# control-bridge.net
KiCad netlist of a schematic drawn in EAGLE
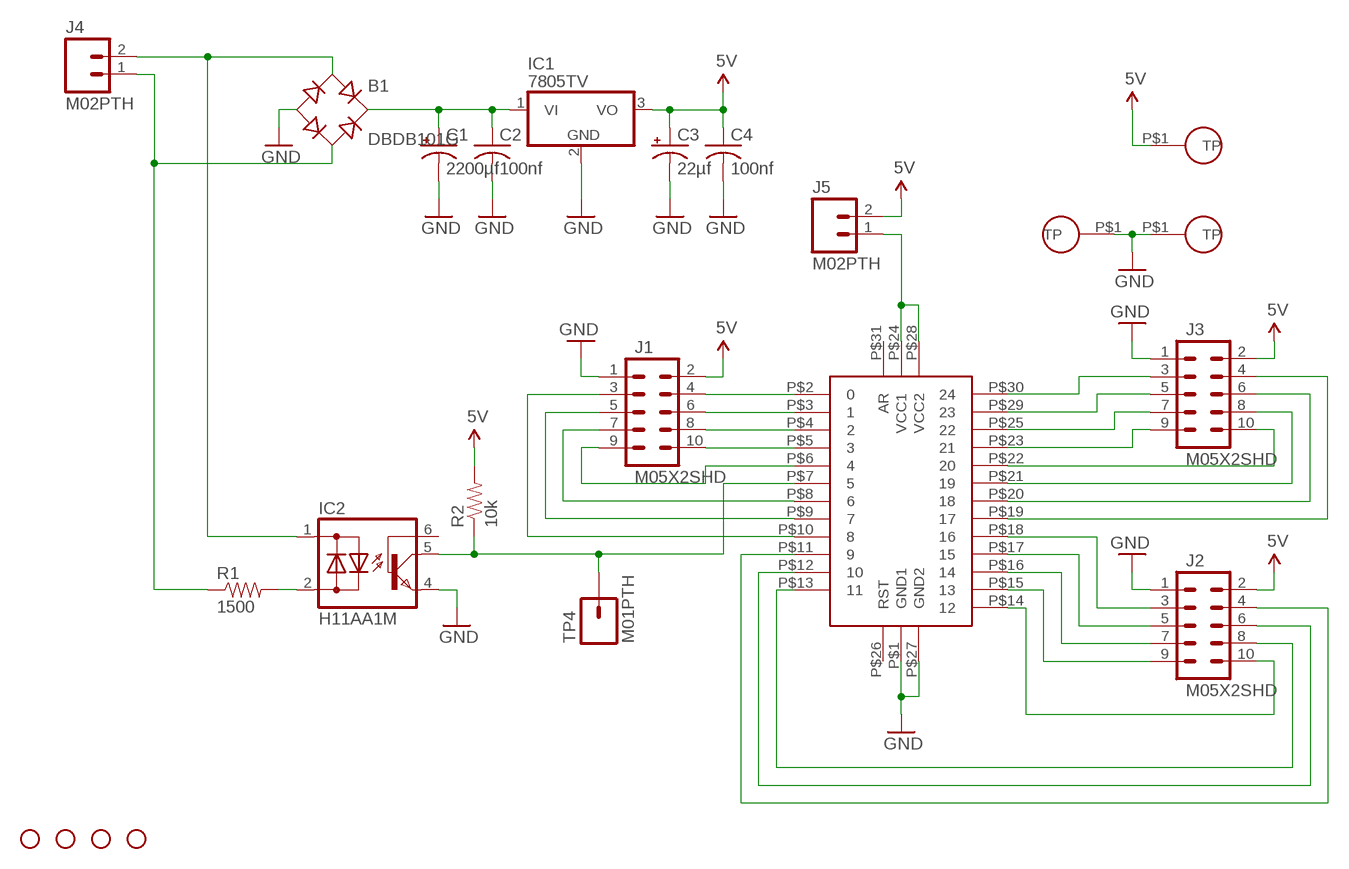
[diagram p0: schematic, sheet 1]

(export (version "E")
  (design (tool "Eeschema 10.0.6"))
  (components
    (comp (ref "B1")
      (value "DBDB101G")
      (footprint "eagle-import:DB")
      (libsource (lib "eagle-import") (part "DB?GDB101"))
    )
    (comp (ref "C1")
      (value "2200µf")
      (footprint "eagle-import:E5-13")
      (libsource (lib "eagle-import") (part "CPOL-USE5-13"))
    )
    (comp (ref "C2")
      (value "100nf")
      (footprint "eagle-import:C025-030X050")
      (libsource (lib "eagle-import") (part "C-US025-030X050"))
    )
    (comp (ref "C3")
      (value "22µf")
      (footprint "eagle-import:E5-8,5")
      (libsource (lib "eagle-import") (part "CPOL-USE5-8.5"))
    )
    (comp (ref "C4")
      (value "100nf")
      (footprint "eagle-import:C025-030X050")
      (libsource (lib "eagle-import") (part "C-US025-030X050"))
    )
    (comp (ref "IC1")
      (value "7805TV")
      (footprint "eagle-import:TO220V")
      (libsource (lib "eagle-import") (part "78TV05"))
    )
    (comp (ref "IC2")
      (value "H11AA1M")
      (footprint "eagle-import:DIL06")
      (fields (field (name "MF") "Fairchild"))
      (libsource (lib "eagle-import") (part "H11AA1M"))
    )
    (comp (ref "J1")
      (value "M05X2SHD")
      (footprint "eagle-import:2X5-SHROUDED")
      (libsource (lib "eagle-import") (part "M05X2SHD"))
    )
    (comp (ref "J2")
      (value "M05X2SHD")
      (footprint "eagle-import:2X5-SHROUDED")
      (libsource (lib "eagle-import") (part "M05X2SHD"))
    )
    (comp (ref "J3")
      (value "M05X2SHD")
      (footprint "eagle-import:2X5-SHROUDED")
      (libsource (lib "eagle-import") (part "M05X2SHD"))
    )
    (comp (ref "J4")
      (value "M02PTH")
      (footprint "eagle-import:1X02")
      (libsource (lib "eagle-import") (part "M02PTH"))
    )
    (comp (ref "J5")
      (value "M02PTH")
      (footprint "eagle-import:1X02")
      (libsource (lib "eagle-import") (part "M02PTH"))
    )
    (comp (ref "R1")
      (value "1500")
      (footprint "eagle-import:AXIAL-0.4")
      (libsource (lib "eagle-import") (part "RESISTORPTH-1/4W"))
    )
    (comp (ref "R2")
      (value "10k")
      (footprint "eagle-import:AXIAL-0.4")
      (libsource (lib "eagle-import") (part "RESISTORPTH-1/4W"))
    )
    (comp (ref "STANDOFF1")
      (value "STAND-OFF")
      (footprint "eagle-import:STAND-OFF")
      (libsource (lib "eagle-import") (part "STAND-OFF"))
    )
    (comp (ref "STANDOFF2")
      (value "STAND-OFF")
      (footprint "eagle-import:STAND-OFF")
      (libsource (lib "eagle-import") (part "STAND-OFF"))
    )
    (comp (ref "STANDOFF3")
      (value "STAND-OFF")
      (footprint "eagle-import:STAND-OFF")
      (libsource (lib "eagle-import") (part "STAND-OFF"))
    )
    (comp (ref "STANDOFF4")
      (value "STAND-OFF")
      (footprint "eagle-import:STAND-OFF")
      (libsource (lib "eagle-import") (part "STAND-OFF"))
    )
    (comp (ref "TP1") (value "TP") (footprint "eagle-import:TP") (libsource (lib "eagle-import") (part "TP")))
    (comp (ref "TP2") (value "TP") (footprint "eagle-import:TP") (libsource (lib "eagle-import") (part "TP")))
    (comp (ref "TP3") (value "TP") (footprint "eagle-import:TP") (libsource (lib "eagle-import") (part "TP")))
    (comp (ref "TP4")
      (value "M01PTH")
      (footprint "eagle-import:1X01")
      (libsource (lib "eagle-import") (part "M01PTH"))
    )
    (comp (ref "U1")
      (value "TEENSY2")
      (footprint "eagle-import:TEENSY2")
      (libsource (lib "eagle-import") (part "TEENSY2"))
    )
  )
  (nets
    (net (code "1") (name "5V") (class "Default")
      (node (ref "C3") (pin "+") (pinfunction "+_+") (pintype "passive"))
      (node (ref "C4") (pin "1") (pinfunction "1_1") (pintype "passive"))
      (node (ref "IC1") (pin "3") (pinfunction "VO_3") (pintype "passive"))
      (node (ref "J1") (pin "2") (pinfunction "2_2") (pintype "passive"))
      (node (ref "J2") (pin "2") (pinfunction "2_2") (pintype "passive"))
      (node (ref "J3") (pin "2") (pinfunction "2_2") (pintype "passive"))
      (node (ref "J5") (pin "2") (pinfunction "2_2") (pintype "passive"))
      (node (ref "R2") (pin "P$2") (pinfunction "2_P$2") (pintype "passive"))
      (node (ref "TP1") (pin "P$1") (pinfunction "TP_P$1") (pintype "input"))
    )
    (net (code "2") (name "GND") (class "Default")
      (node (ref "B1") (pin "-") (pinfunction "-_-") (pintype "passive"))
      (node (ref "C1") (pin "-") (pinfunction "-_-") (pintype "passive"))
      (node (ref "C2") (pin "2") (pinfunction "2_2") (pintype "passive"))
      (node (ref "C3") (pin "-") (pinfunction "-_-") (pintype "passive"))
      (node (ref "C4") (pin "2") (pinfunction "2_2") (pintype "passive"))
      (node (ref "IC1") (pin "2") (pinfunction "GND_2") (pintype "passive"))
      (node (ref "IC2") (pin "4") (pinfunction "E_4") (pintype "passive"))
      (node (ref "J1") (pin "1") (pinfunction "1_1") (pintype "passive"))
      (node (ref "J2") (pin "1") (pinfunction "1_1") (pintype "passive"))
      (node (ref "J3") (pin "1") (pinfunction "1_1") (pintype "passive"))
      (node (ref "TP2") (pin "P$1") (pinfunction "TP_P$1") (pintype "input"))
      (node (ref "TP3") (pin "P$1") (pinfunction "TP_P$1") (pintype "input"))
      (node (ref "U1") (pin "P$1") (pinfunction "GND1_P$1") (pintype "bidirectional"))
      (node (ref "U1") (pin "P$27") (pinfunction "GND2_P$27") (pintype "bidirectional"))
    )
    (net (code "3") (name "Net-(IC1-VI)") (class "Default")
      (node (ref "B1") (pin "+") (pinfunction "+_+") (pintype "passive"))
      (node (ref "C1") (pin "+") (pinfunction "+_+") (pintype "passive"))
      (node (ref "C2") (pin "1") (pinfunction "1_1") (pintype "passive"))
      (node (ref "IC1") (pin "1") (pinfunction "VI_1") (pintype "input"))
    )
    (net (code "4") (name "Net-(IC2-AC1)") (class "Default")
      (node (ref "B1") (pin "AC1") (pinfunction "AC1_AC1") (pintype "passive"))
      (node (ref "IC2") (pin "1") (pinfunction "AC1_1") (pintype "passive"))
      (node (ref "J4") (pin "2") (pinfunction "2_2") (pintype "passive"))
    )
    (net (code "5") (name "Net-(IC2-AC2)") (class "Default")
      (node (ref "IC2") (pin "2") (pinfunction "AC2_2") (pintype "passive"))
      (node (ref "R1") (pin "P$2") (pinfunction "2_P$2") (pintype "passive"))
    )
    (net (code "6") (name "Net-(IC2-C)") (class "Default")
      (node (ref "IC2") (pin "5") (pinfunction "C_5") (pintype "passive"))
      (node (ref "R2") (pin "P$1") (pinfunction "1_P$1") (pintype "passive"))
      (node (ref "TP4") (pin "1") (pinfunction "1_1") (pintype "passive"))
      (node (ref "U1") (pin "P$7") (pinfunction "5_P$7") (pintype "bidirectional"))
    )
    (net (code "7") (name "Net-(R1-1)") (class "Default")
      (node (ref "B1") (pin "AC2") (pinfunction "AC2_AC2") (pintype "passive"))
      (node (ref "J4") (pin "1") (pinfunction "1_1") (pintype "passive"))
      (node (ref "R1") (pin "P$1") (pinfunction "1_P$1") (pintype "passive"))
    )
    (net (code "8") (name "Net-(U1-0)") (class "Default")
      (node (ref "J1") (pin "4") (pinfunction "4_4") (pintype "passive"))
      (node (ref "U1") (pin "P$2") (pinfunction "0_P$2") (pintype "bidirectional"))
    )
    (net (code "9") (name "Net-(U1-1)") (class "Default")
      (node (ref "J1") (pin "6") (pinfunction "6_6") (pintype "passive"))
      (node (ref "U1") (pin "P$3") (pinfunction "1_P$3") (pintype "bidirectional"))
    )
    (net (code "10") (name "Net-(U1-2)") (class "Default")
      (node (ref "J1") (pin "8") (pinfunction "8_8") (pintype "passive"))
      (node (ref "U1") (pin "P$4") (pinfunction "2_P$4") (pintype "bidirectional"))
    )
    (net (code "11") (name "Net-(U1-3)") (class "Default")
      (node (ref "J1") (pin "10") (pinfunction "10_10") (pintype "passive"))
      (node (ref "U1") (pin "P$5") (pinfunction "3_P$5") (pintype "bidirectional"))
    )
    (net (code "12") (name "Net-(U1-4)") (class "Default")
      (node (ref "J1") (pin "9") (pinfunction "9_9") (pintype "passive"))
      (node (ref "U1") (pin "P$6") (pinfunction "4_P$6") (pintype "bidirectional"))
    )
    (net (code "13") (name "Net-(U1-6)") (class "Default")
      (node (ref "J1") (pin "7") (pinfunction "7_7") (pintype "passive"))
      (node (ref "U1") (pin "P$8") (pinfunction "6_P$8") (pintype "bidirectional"))
    )
    (net (code "14") (name "Net-(U1-7)") (class "Default")
      (node (ref "J1") (pin "5") (pinfunction "5_5") (pintype "passive"))
      (node (ref "U1") (pin "P$9") (pinfunction "7_P$9") (pintype "bidirectional"))
    )
    (net (code "15") (name "Net-(U1-8)") (class "Default")
      (node (ref "J1") (pin "3") (pinfunction "3_3") (pintype "passive"))
      (node (ref "U1") (pin "P$10") (pinfunction "8_P$10") (pintype "bidirectional"))
    )
    (net (code "16") (name "Net-(U1-9)") (class "Default")
      (node (ref "J2") (pin "4") (pinfunction "4_4") (pintype "passive"))
      (node (ref "U1") (pin "P$11") (pinfunction "9_P$11") (pintype "bidirectional"))
    )
    (net (code "17") (name "Net-(U1-10)") (class "Default")
      (node (ref "J2") (pin "6") (pinfunction "6_6") (pintype "passive"))
      (node (ref "U1") (pin "P$12") (pinfunction "10_P$12") (pintype "bidirectional"))
    )
    (net (code "18") (name "Net-(U1-11)") (class "Default")
      (node (ref "J2") (pin "8") (pinfunction "8_8") (pintype "passive"))
      (node (ref "U1") (pin "P$13") (pinfunction "11_P$13") (pintype "bidirectional"))
    )
    (net (code "19") (name "Net-(U1-12)") (class "Default")
      (node (ref "J2") (pin "10") (pinfunction "10_10") (pintype "passive"))
      (node (ref "U1") (pin "P$14") (pinfunction "12_P$14") (pintype "bidirectional"))
    )
    (net (code "20") (name "Net-(U1-13)") (class "Default")
      (node (ref "J2") (pin "9") (pinfunction "9_9") (pintype "passive"))
      (node (ref "U1") (pin "P$15") (pinfunction "13_P$15") (pintype "bidirectional"))
    )
    (net (code "21") (name "Net-(U1-14)") (class "Default")
      (node (ref "J2") (pin "7") (pinfunction "7_7") (pintype "passive"))
      (node (ref "U1") (pin "P$16") (pinfunction "14_P$16") (pintype "bidirectional"))
    )
    (net (code "22") (name "Net-(U1-15)") (class "Default")
      (node (ref "J2") (pin "5") (pinfunction "5_5") (pintype "passive"))
      (node (ref "U1") (pin "P$17") (pinfunction "15_P$17") (pintype "bidirectional"))
    )
    (net (code "23") (name "Net-(U1-16)") (class "Default")
      (node (ref "J2") (pin "3") (pinfunction "3_3") (pintype "passive"))
      (node (ref "U1") (pin "P$18") (pinfunction "16_P$18") (pintype "bidirectional"))
    )
    (net (code "24") (name "Net-(U1-17)") (class "Default")
      (node (ref "J3") (pin "4") (pinfunction "4_4") (pintype "passive"))
      (node (ref "U1") (pin "P$19") (pinfunction "17_P$19") (pintype "bidirectional"))
    )
    (net (code "25") (name "Net-(U1-18)") (class "Default")
      (node (ref "J3") (pin "6") (pinfunction "6_6") (pintype "passive"))
      (node (ref "U1") (pin "P$20") (pinfunction "18_P$20") (pintype "bidirectional"))
    )
    (net (code "26") (name "Net-(U1-19)") (class "Default")
      (node (ref "J3") (pin "8") (pinfunction "8_8") (pintype "passive"))
      (node (ref "U1") (pin "P$21") (pinfunction "19_P$21") (pintype "bidirectional"))
    )
    (net (code "27") (name "Net-(U1-20)") (class "Default")
      (node (ref "J3") (pin "10") (pinfunction "10_10") (pintype "passive"))
      (node (ref "U1") (pin "P$22") (pinfunction "20_P$22") (pintype "bidirectional"))
    )
    (net (code "28") (name "Net-(U1-21)") (class "Default")
      (node (ref "J3") (pin "9") (pinfunction "9_9") (pintype "passive"))
      (node (ref "U1") (pin "P$23") (pinfunction "21_P$23") (pintype "bidirectional"))
    )
    (net (code "29") (name "Net-(U1-22)") (class "Default")
      (node (ref "J3") (pin "7") (pinfunction "7_7") (pintype "passive"))
      (node (ref "U1") (pin "P$25") (pinfunction "22_P$25") (pintype "bidirectional"))
    )
    (net (code "30") (name "Net-(U1-23)") (class "Default")
      (node (ref "J3") (pin "5") (pinfunction "5_5") (pintype "passive"))
      (node (ref "U1") (pin "P$29") (pinfunction "23_P$29") (pintype "bidirectional"))
    )
    (net (code "31") (name "Net-(U1-24)") (class "Default")
      (node (ref "J3") (pin "3") (pinfunction "3_3") (pintype "passive"))
      (node (ref "U1") (pin "P$30") (pinfunction "24_P$30") (pintype "bidirectional"))
    )
    (net (code "32") (name "Net-(U1-VCC1)") (class "Default")
      (node (ref "J5") (pin "1") (pinfunction "1_1") (pintype "passive"))
      (node (ref "U1") (pin "P$24") (pinfunction "VCC1_P$24") (pintype "bidirectional"))
      (node (ref "U1") (pin "P$28") (pinfunction "VCC2_P$28") (pintype "bidirectional"))
    )
    (net (code "33") (name "unconnected-(IC2-B-Pad6)") (class "Default")
      (node (ref "IC2") (pin "6") (pinfunction "B_6") (pintype "passive"))
    )
    (net (code "34") (name "unconnected-(U1-AR-PadP$31)") (class "Default")
      (node (ref "U1") (pin "P$31") (pinfunction "AR_P$31") (pintype "bidirectional"))
    )
    (net (code "35") (name "unconnected-(U1-RST-PadP$26)") (class "Default")
      (node (ref "U1") (pin "P$26") (pinfunction "RST_P$26") (pintype "bidirectional"))
    )
  )
)
